# inverter.net
KiCad netlist of a schematic drawn in Altium Designer
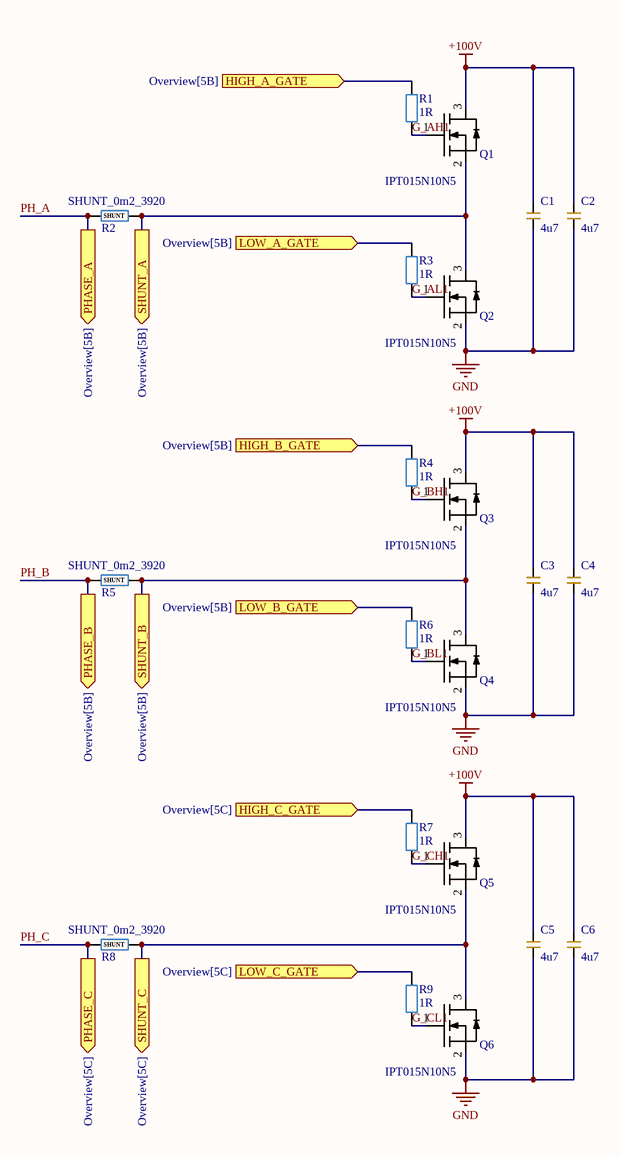
[diagram p0: inverter.SchDoc]

(export (version "E")
  (design (tool "Eeschema 10.0.6"))
  (components
    (comp (ref "C1")
      (value "4u7")
      (footprint "FS32X475K101EGG")
      (description "100V 4.7uF X7R ±10% 1210 Multilayer Ceramic Capacitors MLCC - SMD/SMT ROHS")
      (fields
        (field (name "MFR.") "PSA(Prosperity Dielectrics)")
        (field (name "MFR. PART") "FS32X475K101EGG")
      )
      (libsource (lib "Passive") (part "4u7"))
    )
    (comp (ref "C2")
      (value "4u7")
      (footprint "FS32X475K101EGG")
      (description "100V 4.7uF X7R ±10% 1210 Multilayer Ceramic Capacitors MLCC - SMD/SMT ROHS")
      (fields
        (field (name "MFR.") "PSA(Prosperity Dielectrics)")
        (field (name "MFR. PART") "FS32X475K101EGG")
      )
      (libsource (lib "Passive") (part "4u7"))
    )
    (comp (ref "C3")
      (value "4u7")
      (footprint "FS32X475K101EGG")
      (description "100V 4.7uF X7R ±10% 1210 Multilayer Ceramic Capacitors MLCC - SMD/SMT ROHS")
      (fields
        (field (name "MFR.") "PSA(Prosperity Dielectrics)")
        (field (name "MFR. PART") "FS32X475K101EGG")
      )
      (libsource (lib "Passive") (part "4u7"))
    )
    (comp (ref "C4")
      (value "4u7")
      (footprint "FS32X475K101EGG")
      (description "100V 4.7uF X7R ±10% 1210 Multilayer Ceramic Capacitors MLCC - SMD/SMT ROHS")
      (fields
        (field (name "MFR.") "PSA(Prosperity Dielectrics)")
        (field (name "MFR. PART") "FS32X475K101EGG")
      )
      (libsource (lib "Passive") (part "4u7"))
    )
    (comp (ref "C5")
      (value "4u7")
      (footprint "FS32X475K101EGG")
      (description "100V 4.7uF X7R ±10% 1210 Multilayer Ceramic Capacitors MLCC - SMD/SMT ROHS")
      (fields
        (field (name "MFR.") "PSA(Prosperity Dielectrics)")
        (field (name "MFR. PART") "FS32X475K101EGG")
      )
      (libsource (lib "Passive") (part "4u7"))
    )
    (comp (ref "C6")
      (value "4u7")
      (footprint "FS32X475K101EGG")
      (description "100V 4.7uF X7R ±10% 1210 Multilayer Ceramic Capacitors MLCC - SMD/SMT ROHS")
      (fields
        (field (name "MFR.") "PSA(Prosperity Dielectrics)")
        (field (name "MFR. PART") "FS32X475K101EGG")
      )
      (libsource (lib "Passive") (part "4u7"))
    )
    (comp (ref "Q1")
      (value "IPT015N10N5")
      (footprint "IPT015N10N5")
      (description "100V 500A 533W 1.35mΩ 1 N-channel HSOF-8 MOSFETs ROHS")
      (fields (field (name "MFR.") "Tokmas"))
      (libsource (lib "Active") (part "IPT015N10N5"))
    )
    (comp (ref "Q2")
      (value "IPT015N10N5")
      (footprint "IPT015N10N5")
      (description "100V 500A 533W 1.35mΩ 1 N-channel HSOF-8 MOSFETs ROHS")
      (fields (field (name "MFR.") "Tokmas"))
      (libsource (lib "Active") (part "IPT015N10N5"))
    )
    (comp (ref "Q3")
      (value "IPT015N10N5")
      (footprint "IPT015N10N5")
      (description "100V 500A 533W 1.35mΩ 1 N-channel HSOF-8 MOSFETs ROHS")
      (fields (field (name "MFR.") "Tokmas"))
      (libsource (lib "Active") (part "IPT015N10N5"))
    )
    (comp (ref "Q4")
      (value "IPT015N10N5")
      (footprint "IPT015N10N5")
      (description "100V 500A 533W 1.35mΩ 1 N-channel HSOF-8 MOSFETs ROHS")
      (fields (field (name "MFR.") "Tokmas"))
      (libsource (lib "Active") (part "IPT015N10N5"))
    )
    (comp (ref "Q5")
      (value "IPT015N10N5")
      (footprint "IPT015N10N5")
      (description "100V 500A 533W 1.35mΩ 1 N-channel HSOF-8 MOSFETs ROHS")
      (fields (field (name "MFR.") "Tokmas"))
      (libsource (lib "Active") (part "IPT015N10N5"))
    )
    (comp (ref "Q6")
      (value "IPT015N10N5")
      (footprint "IPT015N10N5")
      (description "100V 500A 533W 1.35mΩ 1 N-channel HSOF-8 MOSFETs ROHS")
      (fields (field (name "MFR.") "Tokmas"))
      (libsource (lib "Active") (part "IPT015N10N5"))
    )
    (comp (ref "R1")
      (value "1R")
      (footprint "RES_0805")
      (description "Resistor SMD 0805 Generic")
      (libsource (lib "Passive") (part "RES_0805"))
    )
    (comp (ref "R2")
      (value "SHUNT_0m2_3920")
      (footprint "ASR-M-5-0.2F-t1")
      (description "12W 0.2mΩ Patch Splitter ±200ppm/℃ ±1% 3920 Current Sense Resistors / Shunt Resistors ROHS")
      (fields (field (name "MFR. PART") "ASR-M-5-0.2F-t1") (field (name "MFR.") "Shenzhen Yezhan Elec."))
      (libsource (lib "Passive") (part "SHUNT_0m2_3920"))
    )
    (comp (ref "R3")
      (value "1R")
      (footprint "RES_0805")
      (description "Resistor SMD 0805 Generic")
      (libsource (lib "Passive") (part "RES_0805"))
    )
    (comp (ref "R4")
      (value "1R")
      (footprint "RES_0805")
      (description "Resistor SMD 0805 Generic")
      (libsource (lib "Passive") (part "RES_0805"))
    )
    (comp (ref "R5")
      (value "SHUNT_0m2_3920")
      (footprint "ASR-M-5-0.2F-t1")
      (description "12W 0.2mΩ Patch Splitter ±200ppm/℃ ±1% 3920 Current Sense Resistors / Shunt Resistors ROHS")
      (fields (field (name "MFR. PART") "ASR-M-5-0.2F-t1") (field (name "MFR.") "Shenzhen Yezhan Elec."))
      (libsource (lib "Passive") (part "SHUNT_0m2_3920"))
    )
    (comp (ref "R6")
      (value "1R")
      (footprint "RES_0805")
      (description "Resistor SMD 0805 Generic")
      (libsource (lib "Passive") (part "RES_0805"))
    )
    (comp (ref "R7")
      (value "1R")
      (footprint "RES_0805")
      (description "Resistor SMD 0805 Generic")
      (libsource (lib "Passive") (part "RES_0805"))
    )
    (comp (ref "R8")
      (value "SHUNT_0m2_3920")
      (footprint "ASR-M-5-0.2F-t1")
      (description "12W 0.2mΩ Patch Splitter ±200ppm/℃ ±1% 3920 Current Sense Resistors / Shunt Resistors ROHS")
      (fields (field (name "MFR. PART") "ASR-M-5-0.2F-t1") (field (name "MFR.") "Shenzhen Yezhan Elec."))
      (libsource (lib "Passive") (part "SHUNT_0m2_3920"))
    )
    (comp (ref "R9")
      (value "1R")
      (footprint "RES_0805")
      (description "Resistor SMD 0805 Generic")
      (libsource (lib "Passive") (part "RES_0805"))
    )
  )
  (nets
    (net (code "1") (name "+100V") (class "Default")
      (node (ref "C1") (pin "2") (pintype "passive"))
      (node (ref "C2") (pin "2") (pintype "passive"))
      (node (ref "C3") (pin "2") (pintype "passive"))
      (node (ref "C4") (pin "2") (pintype "passive"))
      (node (ref "C5") (pin "2") (pintype "passive"))
      (node (ref "C6") (pin "2") (pintype "passive"))
      (node (ref "Q1") (pin "3") (pintype "passive"))
      (node (ref "Q3") (pin "3") (pintype "passive"))
      (node (ref "Q5") (pin "3") (pintype "passive"))
    )
    (net (code "2") (name "/G_AH1") (class "Default")
      (node (ref "Q1") (pin "1") (pinfunction "G_1") (pintype "passive"))
      (node (ref "R1") (pin "1") (pintype "passive"))
    )
    (net (code "3") (name "/G_AL1") (class "Default")
      (node (ref "Q2") (pin "1") (pinfunction "G_1") (pintype "passive"))
      (node (ref "R3") (pin "1") (pintype "passive"))
    )
    (net (code "4") (name "/G_BH1") (class "Default")
      (node (ref "Q3") (pin "1") (pinfunction "G_1") (pintype "passive"))
      (node (ref "R4") (pin "1") (pintype "passive"))
    )
    (net (code "5") (name "/G_BL1") (class "Default")
      (node (ref "Q4") (pin "1") (pinfunction "G_1") (pintype "passive"))
      (node (ref "R6") (pin "1") (pintype "passive"))
    )
    (net (code "6") (name "/G_CH1") (class "Default")
      (node (ref "Q5") (pin "1") (pinfunction "G_1") (pintype "passive"))
      (node (ref "R7") (pin "1") (pintype "passive"))
    )
    (net (code "7") (name "/G_CL1") (class "Default")
      (node (ref "Q6") (pin "1") (pinfunction "G_1") (pintype "passive"))
      (node (ref "R9") (pin "1") (pintype "passive"))
    )
    (net (code "8") (name "/HIGH_A_GATE") (class "Default") (node (ref "R1") (pin "2") (pintype "passive")))
    (net (code "9") (name "/HIGH_B_GATE") (class "Default") (node (ref "R4") (pin "2") (pintype "passive")))
    (net (code "10") (name "/HIGH_C_GATE") (class "Default") (node (ref "R7") (pin "2") (pintype "passive")))
    (net (code "11") (name "/LOW_A_GATE") (class "Default") (node (ref "R3") (pin "2") (pintype "passive")))
    (net (code "12") (name "/LOW_B_GATE") (class "Default") (node (ref "R6") (pin "2") (pintype "passive")))
    (net (code "13") (name "/LOW_C_GATE") (class "Default") (node (ref "R9") (pin "2") (pintype "passive")))
    (net (code "14") (name "/PH_A") (class "Default") (node (ref "R2") (pin "1") (pintype "passive")))
    (net (code "15") (name "/PH_B") (class "Default") (node (ref "R5") (pin "1") (pintype "passive")))
    (net (code "16") (name "/PH_C") (class "Default") (node (ref "R8") (pin "1") (pintype "passive")))
    (net (code "17") (name "/SHUNT_A") (class "Default")
      (node (ref "Q1") (pin "2") (pintype "passive"))
      (node (ref "Q2") (pin "3") (pintype "passive"))
      (node (ref "R2") (pin "2") (pintype "passive"))
    )
    (net (code "18") (name "/SHUNT_B") (class "Default")
      (node (ref "Q3") (pin "2") (pintype "passive"))
      (node (ref "Q4") (pin "3") (pintype "passive"))
      (node (ref "R5") (pin "2") (pintype "passive"))
    )
    (net (code "19") (name "/SHUNT_C") (class "Default")
      (node (ref "Q5") (pin "2") (pintype "passive"))
      (node (ref "Q6") (pin "3") (pintype "passive"))
      (node (ref "R8") (pin "2") (pintype "passive"))
    )
    (net (code "20") (name "GND") (class "Default")
      (node (ref "C1") (pin "1") (pintype "passive"))
      (node (ref "C2") (pin "1") (pintype "passive"))
      (node (ref "C3") (pin "1") (pintype "passive"))
      (node (ref "C4") (pin "1") (pintype "passive"))
      (node (ref "C5") (pin "1") (pintype "passive"))
      (node (ref "C6") (pin "1") (pintype "passive"))
      (node (ref "Q2") (pin "2") (pintype "passive"))
      (node (ref "Q4") (pin "2") (pintype "passive"))
      (node (ref "Q6") (pin "2") (pintype "passive"))
    )
  )
)
